# TSOC_RS485_EM_R4_0.net
KiCad netlist of a schematic drawn in EAGLE
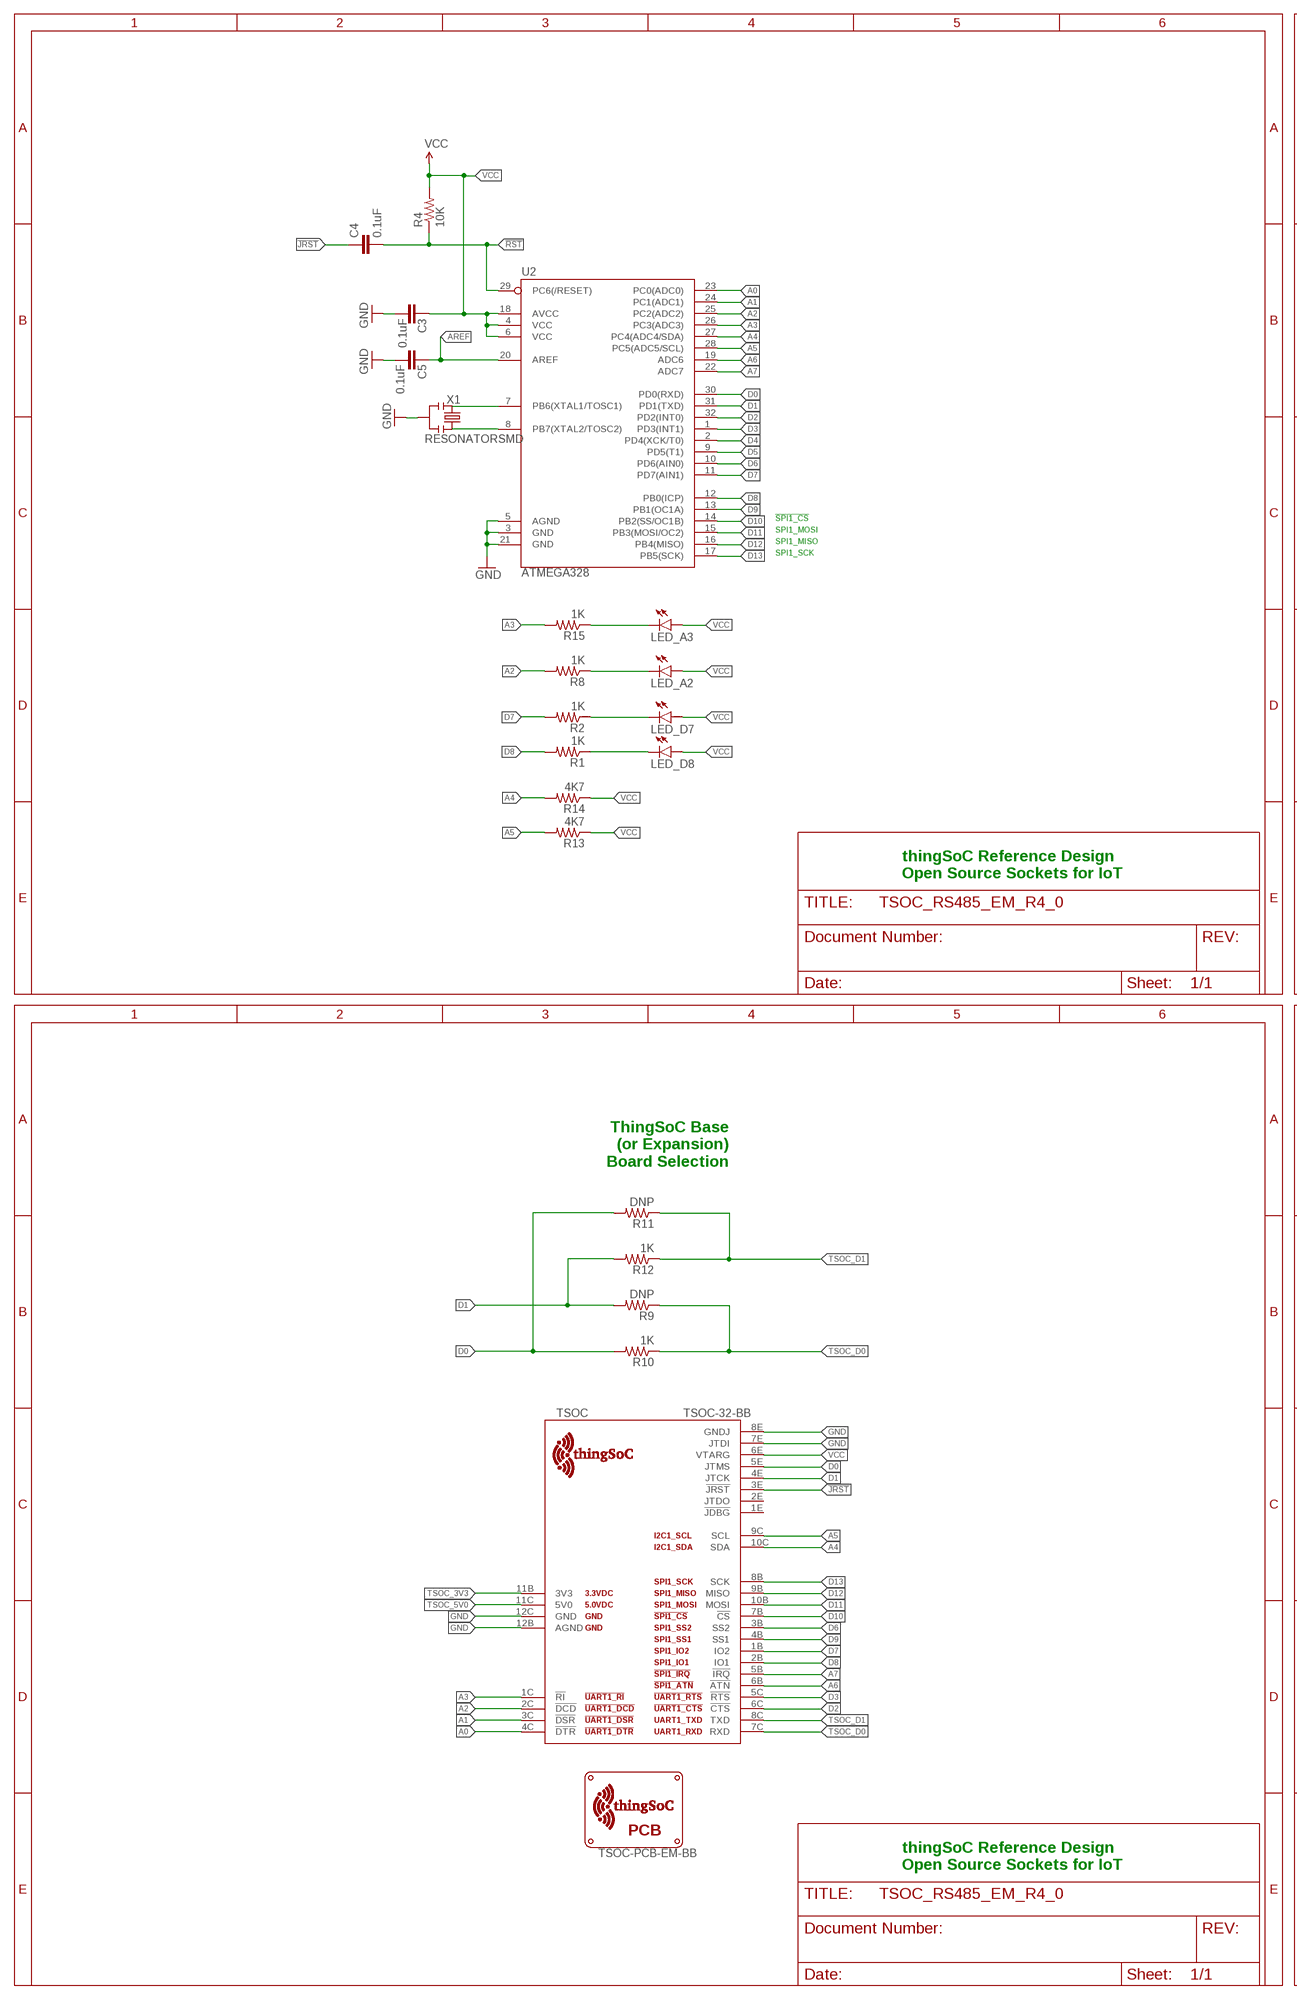
[diagram p0: schematic, sheet 1, part 1 of 2]
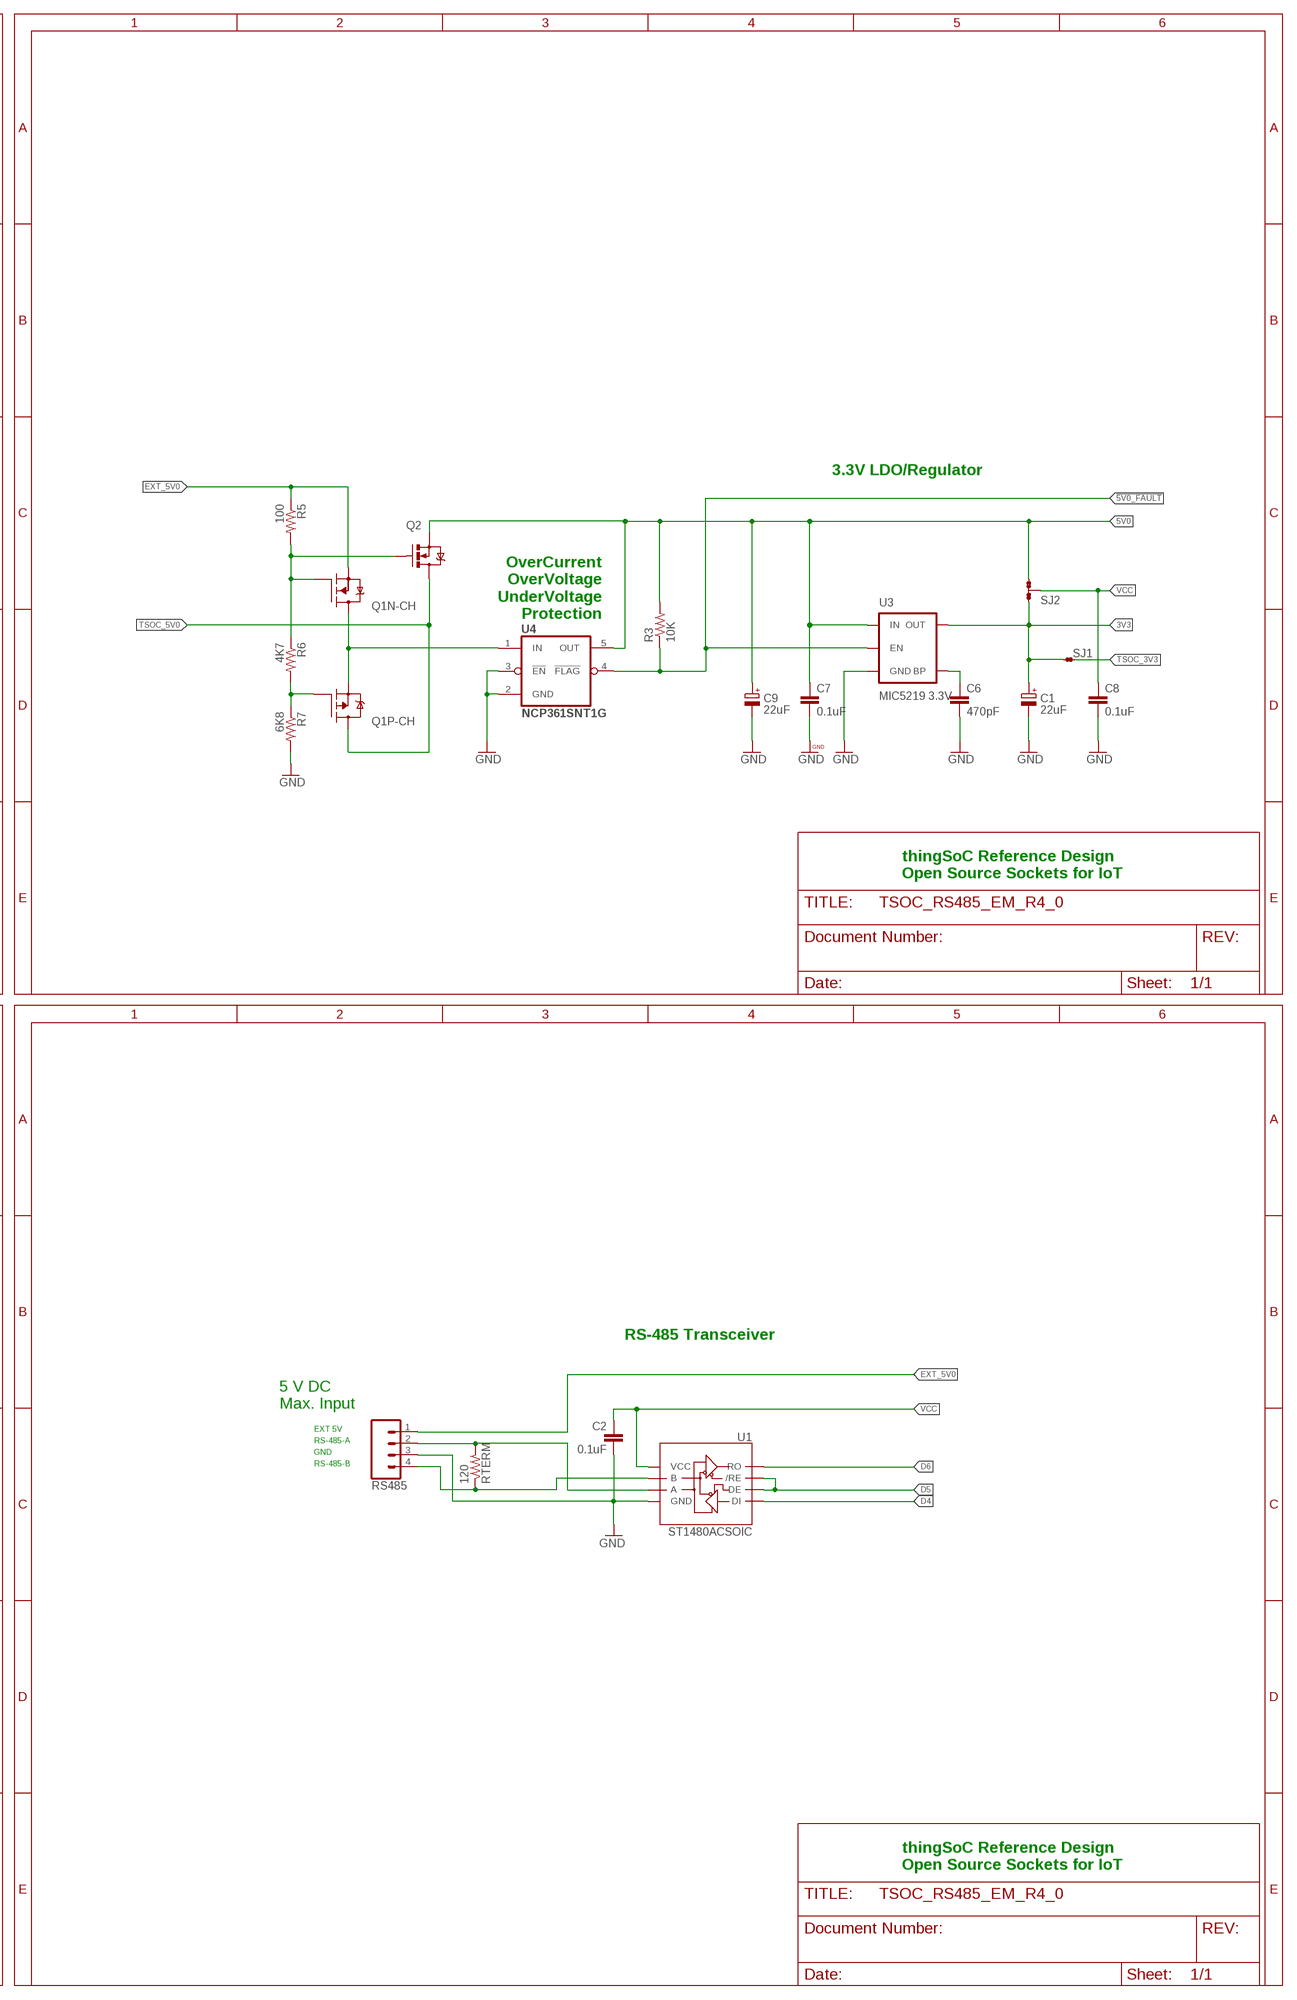
[diagram p1: schematic, sheet 1, part 2 of 2]

(export (version "E")
  (design (tool "Eeschema 10.0.6"))
  (components
    (comp (ref "C1")
      (value "22uF")
      (footprint "eagle-import:SMC_B")
      (libsource (lib "eagle-import") (part "CPOL-EUSMCB"))
    )
    (comp (ref "C2")
      (value "0.1uF")
      (footprint "eagle-import:0402-CAP")
      (libsource (lib "eagle-import") (part "CAP0402-CAP"))
    )
    (comp (ref "C3")
      (value "0.1uF")
      (footprint "eagle-import:0402-CAP")
      (libsource (lib "eagle-import") (part "CAP0402-CAP"))
    )
    (comp (ref "C4")
      (value "0.1uF")
      (footprint "eagle-import:0402-CAP")
      (libsource (lib "eagle-import") (part "CAP0402-CAP"))
    )
    (comp (ref "C5")
      (value "0.1uF")
      (footprint "eagle-import:0402-CAP")
      (libsource (lib "eagle-import") (part "CAP0402-CAP"))
    )
    (comp (ref "C6")
      (value "470pF")
      (footprint "eagle-import:0402-CAP")
      (libsource (lib "eagle-import") (part "CAP0402-CAP"))
    )
    (comp (ref "C7")
      (value "0.1uF")
      (footprint "eagle-import:0402-CAP")
      (libsource (lib "eagle-import") (part "CAP0402-CAP"))
    )
    (comp (ref "C8")
      (value "0.1uF")
      (footprint "eagle-import:0402-CAP")
      (libsource (lib "eagle-import") (part "CAP0402-CAP"))
    )
    (comp (ref "C9")
      (value "22uF")
      (footprint "eagle-import:SMC_B")
      (libsource (lib "eagle-import") (part "CPOL-EUSMCB"))
    )
    (comp (ref "LED_A2")
      (value "LED0603")
      (footprint "eagle-import:LED-0603")
      (libsource (lib "eagle-import") (part "LED0603"))
    )
    (comp (ref "LED_A3")
      (value "LED0603")
      (footprint "eagle-import:LED-0603")
      (libsource (lib "eagle-import") (part "LED0603"))
    )
    (comp (ref "LED_D7")
      (value "LED0603")
      (footprint "eagle-import:LED-0603")
      (libsource (lib "eagle-import") (part "LED0603"))
    )
    (comp (ref "LED_D8")
      (value "LED0603")
      (footprint "eagle-import:LED-0603")
      (libsource (lib "eagle-import") (part "LED0603"))
    )
    (comp (ref "Q1")
      (value "FDC6420C")
      (footprint "eagle-import:SOT95P280X110-6N")
      (libsource (lib "eagle-import") (part "FDC6420C"))
    )
    (comp (ref "Q2")
      (value "MOSFET-NCHANNELAO3404A")
      (footprint "eagle-import:SOT23-3")
      (libsource (lib "eagle-import") (part "MOSFET-NCHANNELAO3404A"))
    )
    (comp (ref "R1")
      (value "1K")
      (footprint "eagle-import:0402-RES")
      (libsource (lib "eagle-import") (part "RESISTOR0402"))
    )
    (comp (ref "R2")
      (value "1K")
      (footprint "eagle-import:0402-RES")
      (libsource (lib "eagle-import") (part "RESISTOR0402"))
    )
    (comp (ref "R3")
      (value "10K")
      (footprint "eagle-import:0402-RES")
      (libsource (lib "eagle-import") (part "RESISTOR0402"))
    )
    (comp (ref "R4")
      (value "10K")
      (footprint "eagle-import:0402-RES")
      (libsource (lib "eagle-import") (part "RESISTOR0402"))
    )
    (comp (ref "R5")
      (value "100")
      (footprint "eagle-import:0402-RES")
      (libsource (lib "eagle-import") (part "RESISTOR0402"))
    )
    (comp (ref "R6")
      (value "4K7")
      (footprint "eagle-import:0402-RES")
      (libsource (lib "eagle-import") (part "RESISTOR0402"))
    )
    (comp (ref "R7")
      (value "6K8")
      (footprint "eagle-import:0402-RES")
      (libsource (lib "eagle-import") (part "RESISTOR0402"))
    )
    (comp (ref "R8")
      (value "1K")
      (footprint "eagle-import:0402-RES")
      (libsource (lib "eagle-import") (part "RESISTOR0402"))
    )
    (comp (ref "R9")
      (value "DNP")
      (footprint "eagle-import:0402-RES")
      (libsource (lib "eagle-import") (part "RESISTOR0402"))
    )
    (comp (ref "R10")
      (value "1K")
      (footprint "eagle-import:0402-RES")
      (libsource (lib "eagle-import") (part "RESISTOR0402"))
    )
    (comp (ref "R11")
      (value "DNP")
      (footprint "eagle-import:0402-RES")
      (libsource (lib "eagle-import") (part "RESISTOR0402"))
    )
    (comp (ref "R12")
      (value "1K")
      (footprint "eagle-import:0402-RES")
      (libsource (lib "eagle-import") (part "RESISTOR0402"))
    )
    (comp (ref "R13")
      (value "4K7")
      (footprint "eagle-import:0402-RES")
      (libsource (lib "eagle-import") (part "RESISTOR0402"))
    )
    (comp (ref "R14")
      (value "4K7")
      (footprint "eagle-import:0402-RES")
      (libsource (lib "eagle-import") (part "RESISTOR0402"))
    )
    (comp (ref "R15")
      (value "1K")
      (footprint "eagle-import:0402-RES")
      (libsource (lib "eagle-import") (part "RESISTOR0402"))
    )
    (comp (ref "RS485")
      (value "M04SCREW")
      (footprint "eagle-import:SCREWTERMINAL-3.5MM-4")
      (libsource (lib "eagle-import") (part "M04SCREW"))
    )
    (comp (ref "RTERM")
      (value "120")
      (footprint "eagle-import:0402-RES")
      (libsource (lib "eagle-import") (part "RESISTOR0402"))
    )
    (comp (ref "SJ1")
      (value "JMP-2-NC")
      (footprint "eagle-import:JMP-2-NC")
      (libsource (lib "eagle-import") (part "JMP-2-NC"))
    )
    (comp (ref "SJ2")
      (value "JMP-3-1_2")
      (footprint "eagle-import:JMP-3-1_2")
      (libsource (lib "eagle-import") (part "JMP-3-1_2"))
    )
    (comp (ref "TSOC")
      (value "TSOC-32-BB")
      (footprint "eagle-import:TSOC-BB-S32")
      (libsource (lib "eagle-import") (part "TSOC-32-BB"))
    )
    (comp (ref "U$1")
      (value "TSOC-PCB-EM-BB")
      (footprint "eagle-import:TSOC-EM-BB")
      (libsource (lib "eagle-import") (part "TSOC-PCB-EM-BB"))
    )
    (comp (ref "U1")
      (value "ST1480ACSOIC")
      (footprint "eagle-import:SO08")
      (libsource (lib "eagle-import") (part "ST1480ACSOIC"))
    )
    (comp (ref "U2")
      (value "ATMEGA328")
      (footprint "eagle-import:TQFP32-08")
      (libsource (lib "eagle-import") (part "ATMEGA168"))
    )
    (comp (ref "U3")
      (value "MIC5219 3.3V")
      (footprint "eagle-import:SOT23-5")
      (libsource (lib "eagle-import") (part "V_REG_MIC52193.3V"))
    )
    (comp (ref "U4")
      (value "NCP361SNT1G")
      (footprint "eagle-import:SOP95P275X110-5N")
      (libsource (lib "eagle-import") (part "NCP361SNT1G"))
    )
    (comp (ref "X1")
      (value "RESONATORSMD")
      (footprint "eagle-import:RESONATOR-SMD")
      (libsource (lib "eagle-import") (part "RESONATORSMD"))
    )
  )
  (nets
    (net (code "1") (name "/~{5V0_FAULT}") (class "Default")
      (node (ref "R3") (pin "1") (pinfunction "1_1") (pintype "passive"))
      (node (ref "U3") (pin "3") (pinfunction "EN_3") (pintype "input"))
      (node (ref "U4") (pin "4") (pinfunction "~{FLAG}_4") (pintype "input"))
    )
    (net (code "2") (name "/~{JRST}") (class "Default")
      (node (ref "C4") (pin "1") (pinfunction "1_1") (pintype "passive"))
      (node (ref "TSOC") (pin "3E") (pinfunction "~{JRST}_3E") (pintype "bidirectional"))
    )
    (net (code "3") (name "/~{RST}") (class "Default")
      (node (ref "C4") (pin "2") (pinfunction "2_2") (pintype "passive"))
      (node (ref "R4") (pin "1") (pinfunction "1_1") (pintype "passive"))
      (node (ref "U2") (pin "29") (pinfunction "PC6(/RESET)_29") (pintype "bidirectional"))
    )
    (net (code "4") (name "3V3") (class "Default")
      (node (ref "C1") (pin "+") (pinfunction "+_+") (pintype "passive"))
      (node (ref "SJ1") (pin "1") (pinfunction "1_1") (pintype "passive"))
      (node (ref "SJ2") (pin "1") (pinfunction "1_1") (pintype "passive"))
      (node (ref "U3") (pin "5") (pinfunction "OUT_5") (pintype "passive"))
    )
    (net (code "5") (name "5V0") (class "Default")
      (node (ref "C7") (pin "1") (pinfunction "1_1") (pintype "passive"))
      (node (ref "C9") (pin "+") (pinfunction "+_+") (pintype "passive"))
      (node (ref "Q2") (pin "2") (pinfunction "S_2") (pintype "passive"))
      (node (ref "R3") (pin "2") (pinfunction "2_2") (pintype "passive"))
      (node (ref "SJ2") (pin "3") (pinfunction "3_3") (pintype "passive"))
      (node (ref "U3") (pin "1") (pinfunction "IN_1") (pintype "input"))
      (node (ref "U4") (pin "5") (pinfunction "OUT_5") (pintype "output"))
    )
    (net (code "6") (name "A0") (class "Default")
      (node (ref "TSOC") (pin "4C") (pinfunction "~{DTR}_4C") (pintype "bidirectional"))
      (node (ref "U2") (pin "23") (pinfunction "PC0(ADC0)_23") (pintype "bidirectional"))
    )
    (net (code "7") (name "A1") (class "Default")
      (node (ref "TSOC") (pin "3C") (pinfunction "~{DSR}_3C") (pintype "bidirectional"))
      (node (ref "U2") (pin "24") (pinfunction "PC1(ADC1)_24") (pintype "bidirectional"))
    )
    (net (code "8") (name "A2") (class "Default")
      (node (ref "R8") (pin "2") (pinfunction "2_2") (pintype "passive"))
      (node (ref "TSOC") (pin "2C") (pinfunction "~{DCD}_2C") (pintype "bidirectional"))
      (node (ref "U2") (pin "25") (pinfunction "PC2(ADC2)_25") (pintype "bidirectional"))
    )
    (net (code "9") (name "A3") (class "Default")
      (node (ref "R15") (pin "2") (pinfunction "2_2") (pintype "passive"))
      (node (ref "TSOC") (pin "1C") (pinfunction "~{RI}_1C") (pintype "bidirectional"))
      (node (ref "U2") (pin "26") (pinfunction "PC3(ADC3)_26") (pintype "bidirectional"))
    )
    (net (code "10") (name "A4") (class "Default")
      (node (ref "R14") (pin "2") (pinfunction "2_2") (pintype "passive"))
      (node (ref "TSOC") (pin "10C") (pinfunction "SDA_10C") (pintype "bidirectional"))
      (node (ref "U2") (pin "27") (pinfunction "PC4(ADC4/SDA)_27") (pintype "bidirectional"))
    )
    (net (code "11") (name "A5") (class "Default")
      (node (ref "R13") (pin "2") (pinfunction "2_2") (pintype "passive"))
      (node (ref "TSOC") (pin "9C") (pinfunction "SCL_9C") (pintype "bidirectional"))
      (node (ref "U2") (pin "28") (pinfunction "PC5(ADC5/SCL)_28") (pintype "bidirectional"))
    )
    (net (code "12") (name "A6") (class "Default")
      (node (ref "TSOC") (pin "6B") (pinfunction "~{ATN}_6B") (pintype "bidirectional"))
      (node (ref "U2") (pin "19") (pinfunction "ADC6_19") (pintype "bidirectional"))
    )
    (net (code "13") (name "A7") (class "Default")
      (node (ref "TSOC") (pin "5B") (pinfunction "~{IRQ}_5B") (pintype "bidirectional"))
      (node (ref "U2") (pin "22") (pinfunction "ADC7_22") (pintype "bidirectional"))
    )
    (net (code "14") (name "AREF") (class "Default")
      (node (ref "C5") (pin "2") (pinfunction "2_2") (pintype "passive"))
      (node (ref "U2") (pin "20") (pinfunction "AREF_20") (pintype "bidirectional"))
    )
    (net (code "15") (name "D0") (class "Default")
      (node (ref "R10") (pin "2") (pinfunction "2_2") (pintype "passive"))
      (node (ref "R11") (pin "2") (pinfunction "2_2") (pintype "passive"))
      (node (ref "TSOC") (pin "5E") (pinfunction "JTMS_5E") (pintype "bidirectional"))
      (node (ref "U2") (pin "30") (pinfunction "PD0(RXD)_30") (pintype "bidirectional"))
    )
    (net (code "16") (name "D1") (class "Default")
      (node (ref "R12") (pin "2") (pinfunction "2_2") (pintype "passive"))
      (node (ref "R9") (pin "2") (pinfunction "2_2") (pintype "passive"))
      (node (ref "TSOC") (pin "4E") (pinfunction "JTCK_4E") (pintype "bidirectional"))
      (node (ref "U2") (pin "31") (pinfunction "PD1(TXD)_31") (pintype "bidirectional"))
    )
    (net (code "17") (name "D2") (class "Default")
      (node (ref "TSOC") (pin "6C") (pinfunction "~{CTS}_6C") (pintype "bidirectional"))
      (node (ref "U2") (pin "32") (pinfunction "PD2(INT0)_32") (pintype "bidirectional"))
    )
    (net (code "18") (name "D3") (class "Default")
      (node (ref "TSOC") (pin "5C") (pinfunction "~{RTS}_5C") (pintype "bidirectional"))
      (node (ref "U2") (pin "1") (pinfunction "PD3(INT1)_1") (pintype "bidirectional"))
    )
    (net (code "19") (name "D4") (class "Default")
      (node (ref "U1") (pin "4") (pinfunction "DI_4") (pintype "bidirectional"))
      (node (ref "U2") (pin "2") (pinfunction "PD4(XCK/T0)_2") (pintype "bidirectional"))
    )
    (net (code "20") (name "D5") (class "Default")
      (node (ref "U1") (pin "2") (pinfunction "/RE_2") (pintype "bidirectional"))
      (node (ref "U1") (pin "3") (pinfunction "DE_3") (pintype "bidirectional"))
      (node (ref "U2") (pin "9") (pinfunction "PD5(T1)_9") (pintype "bidirectional"))
    )
    (net (code "21") (name "D6") (class "Default")
      (node (ref "TSOC") (pin "3B") (pinfunction "SS2_3B") (pintype "bidirectional"))
      (node (ref "U1") (pin "1") (pinfunction "RO_1") (pintype "bidirectional"))
      (node (ref "U2") (pin "10") (pinfunction "PD6(AIN0)_10") (pintype "bidirectional"))
    )
    (net (code "22") (name "D7") (class "Default")
      (node (ref "R2") (pin "2") (pinfunction "2_2") (pintype "passive"))
      (node (ref "TSOC") (pin "1B") (pinfunction "IO2_1B") (pintype "bidirectional"))
      (node (ref "U2") (pin "11") (pinfunction "PD7(AIN1)_11") (pintype "bidirectional"))
    )
    (net (code "23") (name "D8") (class "Default")
      (node (ref "R1") (pin "2") (pinfunction "2_2") (pintype "passive"))
      (node (ref "TSOC") (pin "2B") (pinfunction "IO1_2B") (pintype "bidirectional"))
      (node (ref "U2") (pin "12") (pinfunction "PB0(ICP)_12") (pintype "bidirectional"))
    )
    (net (code "24") (name "D9") (class "Default")
      (node (ref "TSOC") (pin "4B") (pinfunction "SS1_4B") (pintype "bidirectional"))
      (node (ref "U2") (pin "13") (pinfunction "PB1(OC1A)_13") (pintype "bidirectional"))
    )
    (net (code "25") (name "D10") (class "Default")
      (node (ref "TSOC") (pin "7B") (pinfunction "~{CS}_7B") (pintype "bidirectional"))
      (node (ref "U2") (pin "14") (pinfunction "PB2(SS/OC1B)_14") (pintype "bidirectional"))
    )
    (net (code "26") (name "D11") (class "Default")
      (node (ref "TSOC") (pin "10B") (pinfunction "MOSI_10B") (pintype "bidirectional"))
      (node (ref "U2") (pin "15") (pinfunction "PB3(MOSI/OC2)_15") (pintype "bidirectional"))
    )
    (net (code "27") (name "D12") (class "Default")
      (node (ref "TSOC") (pin "9B") (pinfunction "MISO_9B") (pintype "bidirectional"))
      (node (ref "U2") (pin "16") (pinfunction "PB4(MISO)_16") (pintype "bidirectional"))
    )
    (net (code "28") (name "D13") (class "Default")
      (node (ref "TSOC") (pin "8B") (pinfunction "SCK_8B") (pintype "bidirectional"))
      (node (ref "U2") (pin "17") (pinfunction "PB5(SCK)_17") (pintype "bidirectional"))
    )
    (net (code "29") (name "EXT_5V0") (class "Default")
      (node (ref "Q1") (pin "5") (pinfunction "S_5") (pintype "passive"))
      (node (ref "R5") (pin "1") (pinfunction "1_1") (pintype "passive"))
      (node (ref "RS485") (pin "1") (pinfunction "1_1") (pintype "passive"))
    )
    (net (code "30") (name "GND") (class "Default")
      (node (ref "C1") (pin "-") (pinfunction "-_-") (pintype "passive"))
      (node (ref "C2") (pin "2") (pinfunction "2_2") (pintype "passive"))
      (node (ref "C3") (pin "1") (pinfunction "1_1") (pintype "passive"))
      (node (ref "C5") (pin "1") (pinfunction "1_1") (pintype "passive"))
      (node (ref "C6") (pin "2") (pinfunction "2_2") (pintype "passive"))
      (node (ref "C7") (pin "2") (pinfunction "2_2") (pintype "passive"))
      (node (ref "C8") (pin "2") (pinfunction "2_2") (pintype "passive"))
      (node (ref "C9") (pin "-") (pinfunction "-_-") (pintype "passive"))
      (node (ref "R7") (pin "2") (pinfunction "2_2") (pintype "passive"))
      (node (ref "RS485") (pin "3") (pinfunction "3_3") (pintype "passive"))
      (node (ref "TSOC") (pin "12B") (pinfunction "AGND_12B") (pintype "bidirectional"))
      (node (ref "TSOC") (pin "12C") (pinfunction "GND_12C") (pintype "bidirectional"))
      (node (ref "TSOC") (pin "7E") (pinfunction "JTDI_7E") (pintype "bidirectional"))
      (node (ref "TSOC") (pin "8E") (pinfunction "GNDJ_8E") (pintype "bidirectional"))
      (node (ref "U1") (pin "5") (pinfunction "GND_5") (pintype "bidirectional"))
      (node (ref "U2") (pin "21") (pinfunction "GND_21") (pintype "bidirectional"))
      (node (ref "U2") (pin "3") (pinfunction "GND_3") (pintype "bidirectional"))
      (node (ref "U2") (pin "5") (pinfunction "AGND_5") (pintype "bidirectional"))
      (node (ref "U3") (pin "2") (pinfunction "GND_2") (pintype "input"))
      (node (ref "U4") (pin "2") (pinfunction "GND_2") (pintype "passive"))
      (node (ref "U4") (pin "3") (pinfunction "~{EN}_3") (pintype "input"))
      (node (ref "X1") (pin "2") (pinfunction "2_2") (pintype "passive"))
    )
    (net (code "31") (name "Net-(LED_A2-PadC)") (class "Default")
      (node (ref "LED_A2") (pin "C") (pinfunction "C_C") (pintype "passive"))
      (node (ref "R8") (pin "1") (pinfunction "1_1") (pintype "passive"))
    )
    (net (code "32") (name "Net-(LED_A3-PadC)") (class "Default")
      (node (ref "LED_A3") (pin "C") (pinfunction "C_C") (pintype "passive"))
      (node (ref "R15") (pin "1") (pinfunction "1_1") (pintype "passive"))
    )
    (net (code "33") (name "Net-(LED_D7-PadC)") (class "Default")
      (node (ref "LED_D7") (pin "C") (pinfunction "C_C") (pintype "passive"))
      (node (ref "R2") (pin "1") (pinfunction "1_1") (pintype "passive"))
    )
    (net (code "34") (name "Net-(LED_D8-PadC)") (class "Default")
      (node (ref "LED_D8") (pin "C") (pinfunction "C_C") (pintype "passive"))
      (node (ref "R1") (pin "1") (pinfunction "1_1") (pintype "passive"))
    )
    (net (code "35") (name "Net-(Q1A-D)") (class "Default")
      (node (ref "Q1") (pin "2") (pinfunction "S_2") (pintype "passive"))
      (node (ref "Q1") (pin "6") (pinfunction "D_6") (pintype "passive"))
      (node (ref "U4") (pin "1") (pinfunction "IN_1") (pintype "power_in"))
    )
    (net (code "36") (name "Net-(Q1A-G)") (class "Default")
      (node (ref "Q1") (pin "1") (pinfunction "G_1") (pintype "passive"))
      (node (ref "Q2") (pin "1") (pinfunction "G_1") (pintype "passive"))
      (node (ref "R5") (pin "2") (pinfunction "2_2") (pintype "passive"))
      (node (ref "R6") (pin "1") (pinfunction "1_1") (pintype "passive"))
    )
    (net (code "37") (name "Net-(Q1B-G)") (class "Default")
      (node (ref "Q1") (pin "3") (pinfunction "G_3") (pintype "passive"))
      (node (ref "R6") (pin "2") (pinfunction "2_2") (pintype "passive"))
      (node (ref "R7") (pin "1") (pinfunction "1_1") (pintype "passive"))
    )
    (net (code "38") (name "Net-(U1-A)") (class "Default")
      (node (ref "RS485") (pin "2") (pinfunction "2_2") (pintype "passive"))
      (node (ref "RTERM") (pin "2") (pinfunction "2_2") (pintype "passive"))
      (node (ref "U1") (pin "6") (pinfunction "A_6") (pintype "bidirectional"))
    )
    (net (code "39") (name "Net-(U1-B)") (class "Default")
      (node (ref "RS485") (pin "4") (pinfunction "4_4") (pintype "passive"))
      (node (ref "RTERM") (pin "1") (pinfunction "1_1") (pintype "passive"))
      (node (ref "U1") (pin "7") (pinfunction "B_7") (pintype "bidirectional"))
    )
    (net (code "40") (name "Net-(U2-PB6(XTAL1{slash}TOSC1))") (class "Default")
      (node (ref "U2") (pin "7") (pinfunction "PB6(XTAL1/TOSC1)_7") (pintype "bidirectional"))
      (node (ref "X1") (pin "3") (pinfunction "3_3") (pintype "passive"))
    )
    (net (code "41") (name "Net-(U2-PB7(XTAL2{slash}TOSC2))") (class "Default")
      (node (ref "U2") (pin "8") (pinfunction "PB7(XTAL2/TOSC2)_8") (pintype "bidirectional"))
      (node (ref "X1") (pin "1") (pinfunction "1_1") (pintype "passive"))
    )
    (net (code "42") (name "Net-(U3-BP)") (class "Default")
      (node (ref "C6") (pin "1") (pinfunction "1_1") (pintype "passive"))
      (node (ref "U3") (pin "4") (pinfunction "BP_4") (pintype "input"))
    )
    (net (code "43") (name "TSOC_3V3") (class "Default")
      (node (ref "SJ1") (pin "2") (pinfunction "2_2") (pintype "passive"))
      (node (ref "TSOC") (pin "11B") (pinfunction "3V3_11B") (pintype "bidirectional"))
    )
    (net (code "44") (name "TSOC_5V0") (class "Default")
      (node (ref "Q1") (pin "4") (pinfunction "D_4") (pintype "passive"))
      (node (ref "Q2") (pin "3") (pinfunction "D_3") (pintype "passive"))
      (node (ref "TSOC") (pin "11C") (pinfunction "5V0_11C") (pintype "bidirectional"))
    )
    (net (code "45") (name "TSOC_D0") (class "Default")
      (node (ref "R10") (pin "1") (pinfunction "1_1") (pintype "passive"))
      (node (ref "R9") (pin "1") (pinfunction "1_1") (pintype "passive"))
      (node (ref "TSOC") (pin "7C") (pinfunction "RXD_7C") (pintype "bidirectional"))
    )
    (net (code "46") (name "TSOC_D1") (class "Default")
      (node (ref "R11") (pin "1") (pinfunction "1_1") (pintype "passive"))
      (node (ref "R12") (pin "1") (pinfunction "1_1") (pintype "passive"))
      (node (ref "TSOC") (pin "8C") (pinfunction "TXD_8C") (pintype "bidirectional"))
    )
    (net (code "47") (name "VCC") (class "Default")
      (node (ref "C2") (pin "1") (pinfunction "1_1") (pintype "passive"))
      (node (ref "C3") (pin "2") (pinfunction "2_2") (pintype "passive"))
      (node (ref "C8") (pin "1") (pinfunction "1_1") (pintype "passive"))
      (node (ref "LED_A2") (pin "A") (pinfunction "A_A") (pintype "passive"))
      (node (ref "LED_A3") (pin "A") (pinfunction "A_A") (pintype "passive"))
      (node (ref "LED_D7") (pin "A") (pinfunction "A_A") (pintype "passive"))
      (node (ref "LED_D8") (pin "A") (pinfunction "A_A") (pintype "passive"))
      (node (ref "R13") (pin "1") (pinfunction "1_1") (pintype "passive"))
      (node (ref "R14") (pin "1") (pinfunction "1_1") (pintype "passive"))
      (node (ref "R4") (pin "2") (pinfunction "2_2") (pintype "passive"))
      (node (ref "SJ2") (pin "2") (pinfunction "2_2") (pintype "passive"))
      (node (ref "TSOC") (pin "6E") (pinfunction "VTARG_6E") (pintype "bidirectional"))
      (node (ref "U1") (pin "8") (pinfunction "VCC_8") (pintype "bidirectional"))
      (node (ref "U2") (pin "18") (pinfunction "AVCC_18") (pintype "bidirectional"))
      (node (ref "U2") (pin "4") (pinfunction "VCC_4") (pintype "bidirectional"))
      (node (ref "U2") (pin "6") (pinfunction "VCC_6") (pintype "bidirectional"))
    )
    (net (code "48") (name "unconnected-(TSOC-JTDO-Pad2E)") (class "Default")
      (node (ref "TSOC") (pin "2E") (pinfunction "JTDO_2E") (pintype "bidirectional"))
    )
    (net (code "49") (name "unconnected-(TSOC-~{JDBG}-Pad1E)") (class "Default")
      (node (ref "TSOC") (pin "1E") (pinfunction "~{JDBG}_1E") (pintype "bidirectional"))
    )
  )
)
